# Sheet.net
KiCad netlist of a schematic drawn in Altium Designer
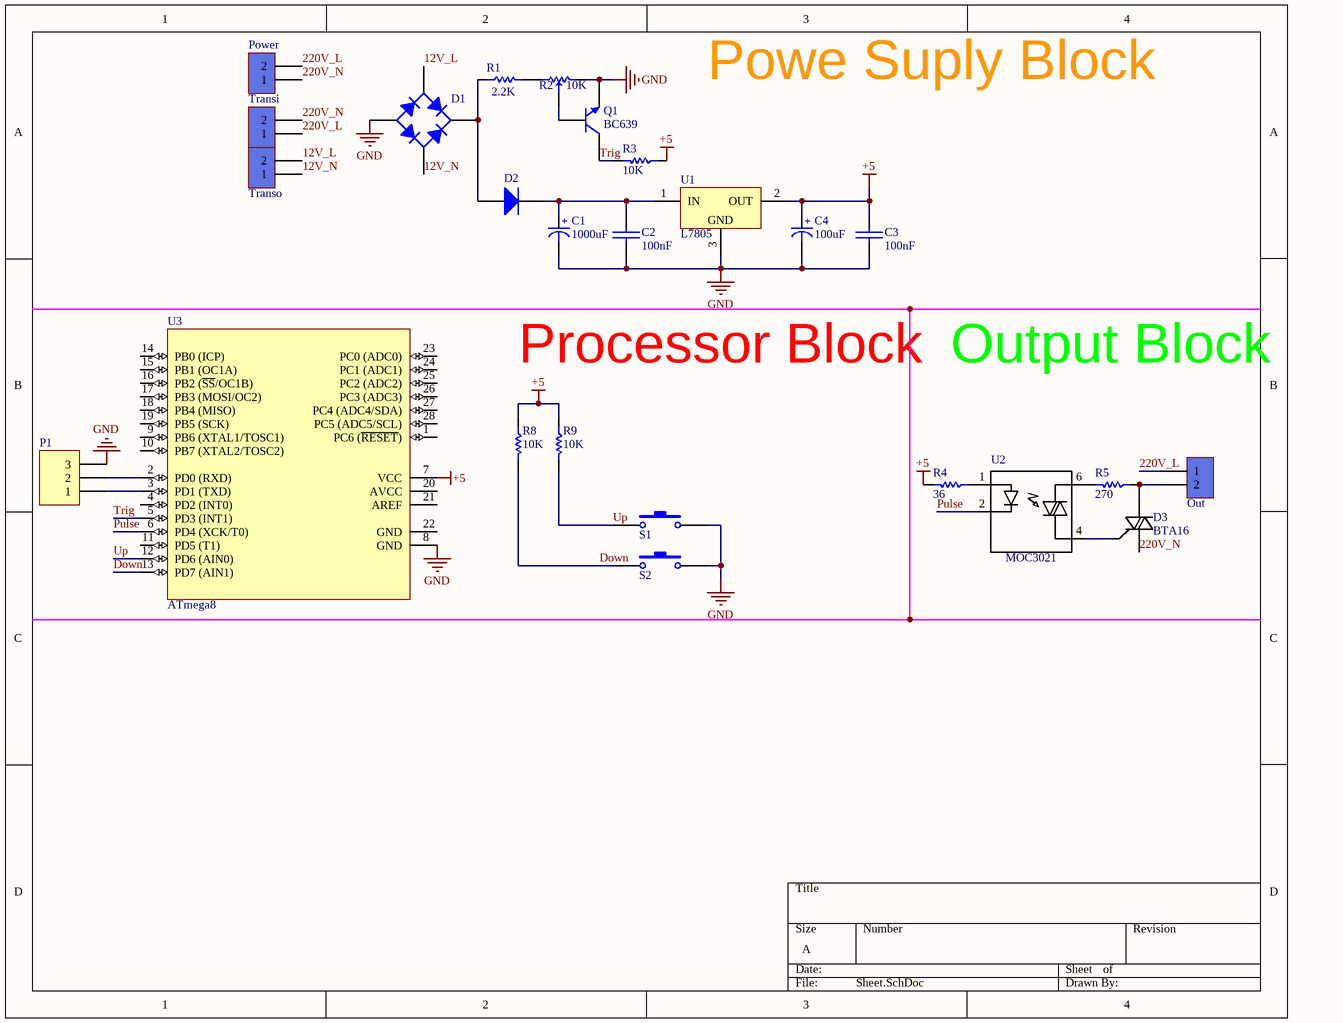
[diagram p0: Sheet.SchDoc]

(export (version "E")
  (design (tool "Eeschema 10.0.6"))
  (components
    (comp (ref "C1")
      (value "1000uF")
      (footprint "cap 04")
      (description "Polar Capacitor")
      (fields (field (name "VOLTAGE") "25V") (field (name "DESIGNER") "Saeid Jorablo"))
      (libsource (lib "My_Library") (part "Cap-Polar"))
    )
    (comp (ref "C2")
      (value "100nF")
      (footprint "Cap - 100nF")
      (description "Bipolar Capacitor")
      (fields (field (name "VOLTAGE") "100V") (field (name "DESIGNER") "Saeid Jorablo"))
      (libsource (lib "My_Library") (part "Cap-Bipolar"))
    )
    (comp (ref "C3")
      (value "100nF")
      (footprint "Cap - 100nF")
      (description "Bipolar Capacitor")
      (fields (field (name "VOLTAGE") "100V") (field (name "DESIGNER") "Saeid Jorablo"))
      (libsource (lib "My_Library") (part "Cap-Bipolar"))
    )
    (comp (ref "C4")
      (value "100uF")
      (footprint "cap 03")
      (description "Polar Capacitor")
      (fields (field (name "VOLTAGE") "25V") (field (name "DESIGNER") "Saeid Jorablo"))
      (libsource (lib "My_Library") (part "Cap-Polar"))
    )
    (comp (ref "D1")
      (value "Diode Bridge")
      (footprint "Bridge")
      (description "Full Wave Diode Bridge")
      (libsource (lib "My_Library") (part "Diode Bridge"))
    )
    (comp (ref "D2")
      (value "Diode 1N4007")
      (footprint "DO-41")
      (description "1 Amp General Purpose Rectifier")
      (fields (field (name "PUBLISHER") "Altium Limited"))
      (libsource (lib "Miscellaneous Devices") (part "Diode 1N4007"))
    )
    (comp (ref "D3")
      (value "BTA16")
      (footprint "*TO254P1028X482X1968-3")
      (description "Thyristor TRIAC 600V 170A 3-Pin_3+Tab_ TO-220AB Tube")
      (fields (field (name "MF") "Littelfuse Inc.") (field (name "MP") "BTA16-600CW3G"))
      (libsource (lib "BTA16") (part "BTA16-600CW3G"))
    )
    (comp (ref "Out")
      (value "Terminal")
      (footprint "Terminal 1*2")
      (description "Terminal 2 Pin 250VAC 16A")
      (fields (field (name "DESIGNER") "Seyed Mohsen Ghasemain") (field (name "E-MAIL") "picpars@gmail.com"))
      (libsource (lib "") (part "Terminal 1*2_1"))
    )
    (comp (ref "P1")
      (value "MHDR1X3")
      (footprint "MHDR1X3")
      (description "Header, 3-Pin")
      (fields (field (name "PUBLISHER") "Altium Limited"))
      (libsource (lib "Miscellaneous Connectors") (part "MHDR1X3"))
    )
    (comp (ref "Power")
      (value "Terminal")
      (footprint "Terminal 1*2")
      (description "Terminal 2 Pin 250VAC 16A")
      (fields (field (name "DESIGNER") "Seyed Mohsen Ghasemain") (field (name "E-MAIL") "picpars@gmail.com"))
      (libsource (lib "usefully_Library") (part "Terminal 1*2"))
    )
    (comp (ref "Q1")
      (value "BC639")
      (footprint "C945")
      (description "NPN Transistor")
      (fields (field (name "DESIGNER") "Saeid Jorablo"))
      (libsource (lib "My_Library") (part "C945"))
    )
    (comp (ref "R1")
      (value "2.2K")
      (footprint "Res-(1/4)")
      (description "Resistor")
      (fields (field (name "TOLERANCE") "5%") (field (name "POWER") "1/8 W"))
      (libsource (lib "My_Library") (part "Resistor"))
    )
    (comp (ref "R2")
      (value "10K")
      (footprint "Pot 00")
      (description "Variable Resistor")
      (fields (field (name "DESIGNER") "Saeid Jorablo"))
      (libsource (lib "My_Library") (part "Resistor Variable"))
    )
    (comp (ref "R3")
      (value "10K")
      (footprint "Res-(1/4)")
      (description "Resistor")
      (fields (field (name "TOLERANCE") "5%") (field (name "POWER") "1/8 W"))
      (libsource (lib "My_Library") (part "Resistor"))
    )
    (comp (ref "R4")
      (value "36")
      (footprint "Res-(1/4)")
      (description "Resistor")
      (fields (field (name "TOLERANCE") "5%") (field (name "POWER") "1/8 W"))
      (libsource (lib "My_Library") (part "Resistor"))
    )
    (comp (ref "R5")
      (value "270")
      (footprint "Res-(1/4)")
      (description "Resistor")
      (fields (field (name "TOLERANCE") "5%") (field (name "POWER") "1/8 W"))
      (libsource (lib "My_Library") (part "Resistor"))
    )
    (comp (ref "R8")
      (value "10K")
      (footprint "Res-(1/4)")
      (description "Resistor")
      (fields (field (name "TOLERANCE") "5%") (field (name "POWER") "1/8 W"))
      (libsource (lib "My_Library") (part "Resistor"))
    )
    (comp (ref "R9")
      (value "10K")
      (footprint "Res-(1/4)")
      (description "Resistor")
      (fields (field (name "TOLERANCE") "5%") (field (name "POWER") "1/8 W"))
      (libsource (lib "My_Library") (part "Resistor"))
    )
    (comp (ref "S1")
      (value "Switch PB")
      (footprint "Switch - Push to On")
      (description "Push Button Switch")
      (libsource (lib "My_Library") (part "Switch PB"))
    )
    (comp (ref "S2")
      (value "Switch PB")
      (footprint "Switch - Push to On")
      (description "Push Button Switch")
      (libsource (lib "My_Library") (part "Switch PB"))
    )
    (comp (ref "Transi")
      (value "Terminal")
      (footprint "Terminal 1*2")
      (description "Terminal 2 Pin 250VAC 16A")
      (fields (field (name "DESIGNER") "Seyed Mohsen Ghasemain") (field (name "E-MAIL") "picpars@gmail.com"))
      (libsource (lib "usefully_Library") (part "Terminal 1*2"))
    )
    (comp (ref "Transo")
      (value "Terminal")
      (footprint "Terminal 1*2")
      (description "Terminal 2 Pin 250VAC 16A")
      (fields (field (name "DESIGNER") "Seyed Mohsen Ghasemain") (field (name "E-MAIL") "picpars@gmail.com"))
      (libsource (lib "usefully_Library") (part "Terminal 1*2"))
    )
    (comp (ref "U1")
      (value "L7805")
      (footprint "78XXCV")
      (description "Fixed Voltage Regulator")
      (fields (field (name "DESIGNER") "Saeid Jorablo"))
      (libsource (lib "My_Library") (part "L78XXCV"))
    )
    (comp (ref "U2")
      (value "MOC3021")
      (footprint "*DIP762W45P254L889H508Q6")
      (description "Optoisolator Triac Output 5300Vrms 1 Channel 6-DIP")
      (fields (field (name "MF") "ON Semiconductor"))
      (libsource (lib "MOC3021") (part "MOC3021"))
    )
    (comp (ref "U3")
      (value "ATmega8")
      (footprint "28P3")
      (description "8-Bit AVR Microcontroller with 8K Bytes of In-System Programmable Flash Memory")
      (fields (field (name "PUBLISHER") "Altium Limited"))
      (libsource (lib "Atmel Microcontroller 8-Bit AVR") (part "ATmega8-16PC"))
    )
  )
  (nets
    (net (code "1") (name "+5") (class "Default")
      (node (ref "C3") (pin "1") (pinfunction "+_1") (pintype "passive"))
      (node (ref "C4") (pin "1") (pinfunction "+_1") (pintype "passive"))
      (node (ref "R3") (pin "1") (pinfunction "1_1") (pintype "passive"))
      (node (ref "R4") (pin "2") (pinfunction "2_2") (pintype "passive"))
      (node (ref "R8") (pin "1") (pinfunction "1_1") (pintype "passive"))
      (node (ref "R9") (pin "1") (pinfunction "1_1") (pintype "passive"))
      (node (ref "U1") (pin "2") (pinfunction "OUT_2") (pintype "passive"))
      (node (ref "U3") (pin "7") (pinfunction "VCC_7") (pintype "power_in"))
    )
    (net (code "2") (name "/12V_L") (class "Default")
      (node (ref "D1") (pin "4") (pinfunction "C_4") (pintype "passive"))
      (node (ref "Transo") (pin "2") (pinfunction "2_2") (pintype "passive"))
    )
    (net (code "3") (name "/12V_N") (class "Default")
      (node (ref "D1") (pin "2") (pinfunction "C_2") (pintype "passive"))
      (node (ref "Transo") (pin "1") (pinfunction "1_1") (pintype "passive"))
    )
    (net (code "4") (name "/220V_L") (class "Default")
      (node (ref "Out") (pin "1") (pinfunction "1_1") (pintype "passive"))
      (node (ref "Power") (pin "2") (pinfunction "2_2") (pintype "passive"))
      (node (ref "Transi") (pin "1") (pinfunction "1_1") (pintype "passive"))
    )
    (net (code "5") (name "/220V_N") (class "Default")
      (node (ref "D3") (pin "1") (pinfunction "MT1_1") (pintype "passive"))
      (node (ref "Power") (pin "1") (pinfunction "1_1") (pintype "passive"))
      (node (ref "Transi") (pin "2") (pinfunction "2_2") (pintype "passive"))
    )
    (net (code "6") (name "/Down") (class "Default")
      (node (ref "R8") (pin "2") (pinfunction "2_2") (pintype "passive"))
      (node (ref "S2") (pin "1") (pinfunction "1_1") (pintype "passive"))
      (node (ref "U3") (pin "13") (pinfunction "PD7_(AIN1)_13") (pintype "bidirectional"))
    )
    (net (code "7") (name "/Pulse") (class "Default")
      (node (ref "U2") (pin "2") (pinfunction "CATODE_2") (pintype "passive"))
      (node (ref "U3") (pin "6") (pinfunction "PD4_(XCK/T0)_6") (pintype "bidirectional"))
    )
    (net (code "8") (name "/Trig") (class "Default")
      (node (ref "Q1") (pin "2") (pinfunction "C_2") (pintype "passive"))
      (node (ref "R3") (pin "2") (pinfunction "2_2") (pintype "passive"))
      (node (ref "U3") (pin "5") (pinfunction "PD3_(INT1)_5") (pintype "bidirectional"))
    )
    (net (code "9") (name "/Up") (class "Default")
      (node (ref "R9") (pin "2") (pinfunction "2_2") (pintype "passive"))
      (node (ref "S1") (pin "1") (pinfunction "1_1") (pintype "passive"))
      (node (ref "U3") (pin "12") (pinfunction "PD6_(AIN0)_12") (pintype "bidirectional"))
    )
    (net (code "10") (name "GND") (class "Default")
      (node (ref "C1") (pin "2") (pinfunction "-_2") (pintype "passive"))
      (node (ref "C2") (pin "2") (pinfunction "-_2") (pintype "passive"))
      (node (ref "C3") (pin "2") (pinfunction "-_2") (pintype "passive"))
      (node (ref "C4") (pin "2") (pinfunction "-_2") (pintype "passive"))
      (node (ref "D1") (pin "3") (pinfunction "A_3") (pintype "passive"))
      (node (ref "P1") (pin "3") (pinfunction "3_3") (pintype "passive"))
      (node (ref "Q1") (pin "1") (pinfunction "E_1") (pintype "passive"))
      (node (ref "R2") (pin "1") (pinfunction "CCW_1") (pintype "passive"))
      (node (ref "S1") (pin "2") (pinfunction "2_2") (pintype "passive"))
      (node (ref "S2") (pin "2") (pinfunction "2_2") (pintype "passive"))
      (node (ref "U1") (pin "3") (pinfunction "GND_3") (pintype "passive"))
      (node (ref "U3") (pin "8") (pinfunction "GND_8") (pintype "power_in"))
    )
    (net (code "11") (name "Net-(C1-+)") (class "Default")
      (node (ref "C1") (pin "1") (pinfunction "+_1") (pintype "passive"))
      (node (ref "C2") (pin "1") (pinfunction "+_1") (pintype "passive"))
      (node (ref "D2") (pin "2") (pinfunction "K_2") (pintype "passive"))
      (node (ref "U1") (pin "1") (pinfunction "IN_1") (pintype "passive"))
    )
    (net (code "12") (name "Net-(D1-K)") (class "Default")
      (node (ref "D1") (pin "1") (pinfunction "K_1") (pintype "passive"))
      (node (ref "D2") (pin "1") (pinfunction "A_1") (pintype "passive"))
      (node (ref "R1") (pin "1") (pinfunction "1_1") (pintype "passive"))
    )
    (net (code "13") (name "Net-(D3-G)") (class "Default")
      (node (ref "D3") (pin "3") (pinfunction "G_3") (pintype "passive"))
      (node (ref "U2") (pin "4") (pinfunction "MAIN_TERM2_4") (pintype "passive"))
    )
    (net (code "14") (name "Net-(D3-MT2)") (class "Default")
      (node (ref "D3") (pin "2") (pinfunction "MT2_2") (pintype "passive"))
      (node (ref "Out") (pin "2") (pinfunction "2_2") (pintype "passive"))
      (node (ref "R5") (pin "1") (pinfunction "1_1") (pintype "passive"))
    )
    (net (code "15") (name "Net-(Q1-B)") (class "Default")
      (node (ref "Q1") (pin "3") (pinfunction "B_3") (pintype "passive"))
      (node (ref "R2") (pin "3") (pinfunction "Setpoint_3") (pintype "passive"))
    )
    (net (code "16") (name "Net-(R2-CW)") (class "Default")
      (node (ref "R1") (pin "2") (pinfunction "2_2") (pintype "passive"))
      (node (ref "R2") (pin "2") (pinfunction "CW_2") (pintype "passive"))
    )
    (net (code "17") (name "Net-(U2-ANODE)") (class "Default")
      (node (ref "R4") (pin "1") (pinfunction "1_1") (pintype "passive"))
      (node (ref "U2") (pin "1") (pinfunction "ANODE_1") (pintype "passive"))
    )
    (net (code "18") (name "Net-(U2-MAIN_TERM1)") (class "Default")
      (node (ref "R5") (pin "2") (pinfunction "2_2") (pintype "passive"))
      (node (ref "U2") (pin "6") (pinfunction "MAIN_TERM1_6") (pintype "passive"))
    )
    (net (code "19") (name "Net-(U3-PD0_(RXD))") (class "Default")
      (node (ref "P1") (pin "2") (pinfunction "2_2") (pintype "passive"))
      (node (ref "U3") (pin "2") (pinfunction "PD0_(RXD)_2") (pintype "bidirectional"))
    )
    (net (code "20") (name "Net-(U3-PD1_(TXD))") (class "Default")
      (node (ref "P1") (pin "1") (pinfunction "1_1") (pintype "passive"))
      (node (ref "U3") (pin "3") (pinfunction "PD1_(TXD)_3") (pintype "bidirectional"))
    )
    (net (code "21") (name "unconnected-(U3-AREF-Pad21)") (class "Default")
      (node (ref "U3") (pin "21") (pinfunction "AREF_21") (pintype "passive"))
    )
    (net (code "22") (name "unconnected-(U3-AVCC-Pad20)") (class "Default")
      (node (ref "U3") (pin "20") (pinfunction "AVCC_20") (pintype "power_in"))
    )
    (net (code "23") (name "unconnected-(U3-GND-Pad22)") (class "Default")
      (node (ref "U3") (pin "22") (pinfunction "GND_22") (pintype "power_in"))
    )
    (net (code "24") (name "unconnected-(U3-PB0_(ICP)-Pad14)") (class "Default")
      (node (ref "U3") (pin "14") (pinfunction "PB0_(ICP)_14") (pintype "bidirectional"))
    )
    (net (code "25") (name "unconnected-(U3-PB1_(OC1A)-Pad15)") (class "Default")
      (node (ref "U3") (pin "15") (pinfunction "PB1_(OC1A)_15") (pintype "bidirectional"))
    )
    (net (code "26") (name "unconnected-(U3-PB2_(~{SS}{slash}OC1B)-Pad16)") (class "Default")
      (node (ref "U3") (pin "16") (pinfunction "PB2_(~{SS}/OC1B)_16") (pintype "bidirectional"))
    )
    (net (code "27") (name "unconnected-(U3-PB3_(MOSI{slash}OC2)-Pad17)") (class "Default")
      (node (ref "U3") (pin "17") (pinfunction "PB3_(MOSI/OC2)_17") (pintype "bidirectional"))
    )
    (net (code "28") (name "unconnected-(U3-PB4_(MISO)-Pad18)") (class "Default")
      (node (ref "U3") (pin "18") (pinfunction "PB4_(MISO)_18") (pintype "bidirectional"))
    )
    (net (code "29") (name "unconnected-(U3-PB5_(SCK)-Pad19)") (class "Default")
      (node (ref "U3") (pin "19") (pinfunction "PB5_(SCK)_19") (pintype "bidirectional"))
    )
    (net (code "30") (name "unconnected-(U3-PB6_(XTAL1{slash}TOSC1)-Pad9)") (class "Default")
      (node (ref "U3") (pin "9") (pinfunction "PB6_(XTAL1/TOSC1)_9") (pintype "bidirectional"))
    )
    (net (code "31") (name "unconnected-(U3-PB7_(XTAL2{slash}TOSC2)-Pad10)") (class "Default")
      (node (ref "U3") (pin "10") (pinfunction "PB7_(XTAL2/TOSC2)_10") (pintype "bidirectional"))
    )
    (net (code "32") (name "unconnected-(U3-PC0_(ADC0)-Pad23)") (class "Default")
      (node (ref "U3") (pin "23") (pinfunction "PC0_(ADC0)_23") (pintype "bidirectional"))
    )
    (net (code "33") (name "unconnected-(U3-PC1_(ADC1)-Pad24)") (class "Default")
      (node (ref "U3") (pin "24") (pinfunction "PC1_(ADC1)_24") (pintype "bidirectional"))
    )
    (net (code "34") (name "unconnected-(U3-PC2_(ADC2)-Pad25)") (class "Default")
      (node (ref "U3") (pin "25") (pinfunction "PC2_(ADC2)_25") (pintype "bidirectional"))
    )
    (net (code "35") (name "unconnected-(U3-PC3_(ADC3)-Pad26)") (class "Default")
      (node (ref "U3") (pin "26") (pinfunction "PC3_(ADC3)_26") (pintype "bidirectional"))
    )
    (net (code "36") (name "unconnected-(U3-PC4_(ADC4{slash}SDA)-Pad27)") (class "Default")
      (node (ref "U3") (pin "27") (pinfunction "PC4_(ADC4/SDA)_27") (pintype "bidirectional"))
    )
    (net (code "37") (name "unconnected-(U3-PC5_(ADC5{slash}SCL)-Pad28)") (class "Default")
      (node (ref "U3") (pin "28") (pinfunction "PC5_(ADC5/SCL)_28") (pintype "bidirectional"))
    )
    (net (code "38") (name "unconnected-(U3-PC6_(~{RESET})-Pad1)") (class "Default")
      (node (ref "U3") (pin "1") (pinfunction "PC6_(~{RESET})_1") (pintype "bidirectional"))
    )
    (net (code "39") (name "unconnected-(U3-PD2_(INT0)-Pad4)") (class "Default")
      (node (ref "U3") (pin "4") (pinfunction "PD2_(INT0)_4") (pintype "bidirectional"))
    )
    (net (code "40") (name "unconnected-(U3-PD5_(T1)-Pad11)") (class "Default")
      (node (ref "U3") (pin "11") (pinfunction "PD5_(T1)_11") (pintype "bidirectional"))
    )
  )
)
